# Daughter_ESCON.net
KiCad netlist of a schematic drawn in EAGLE
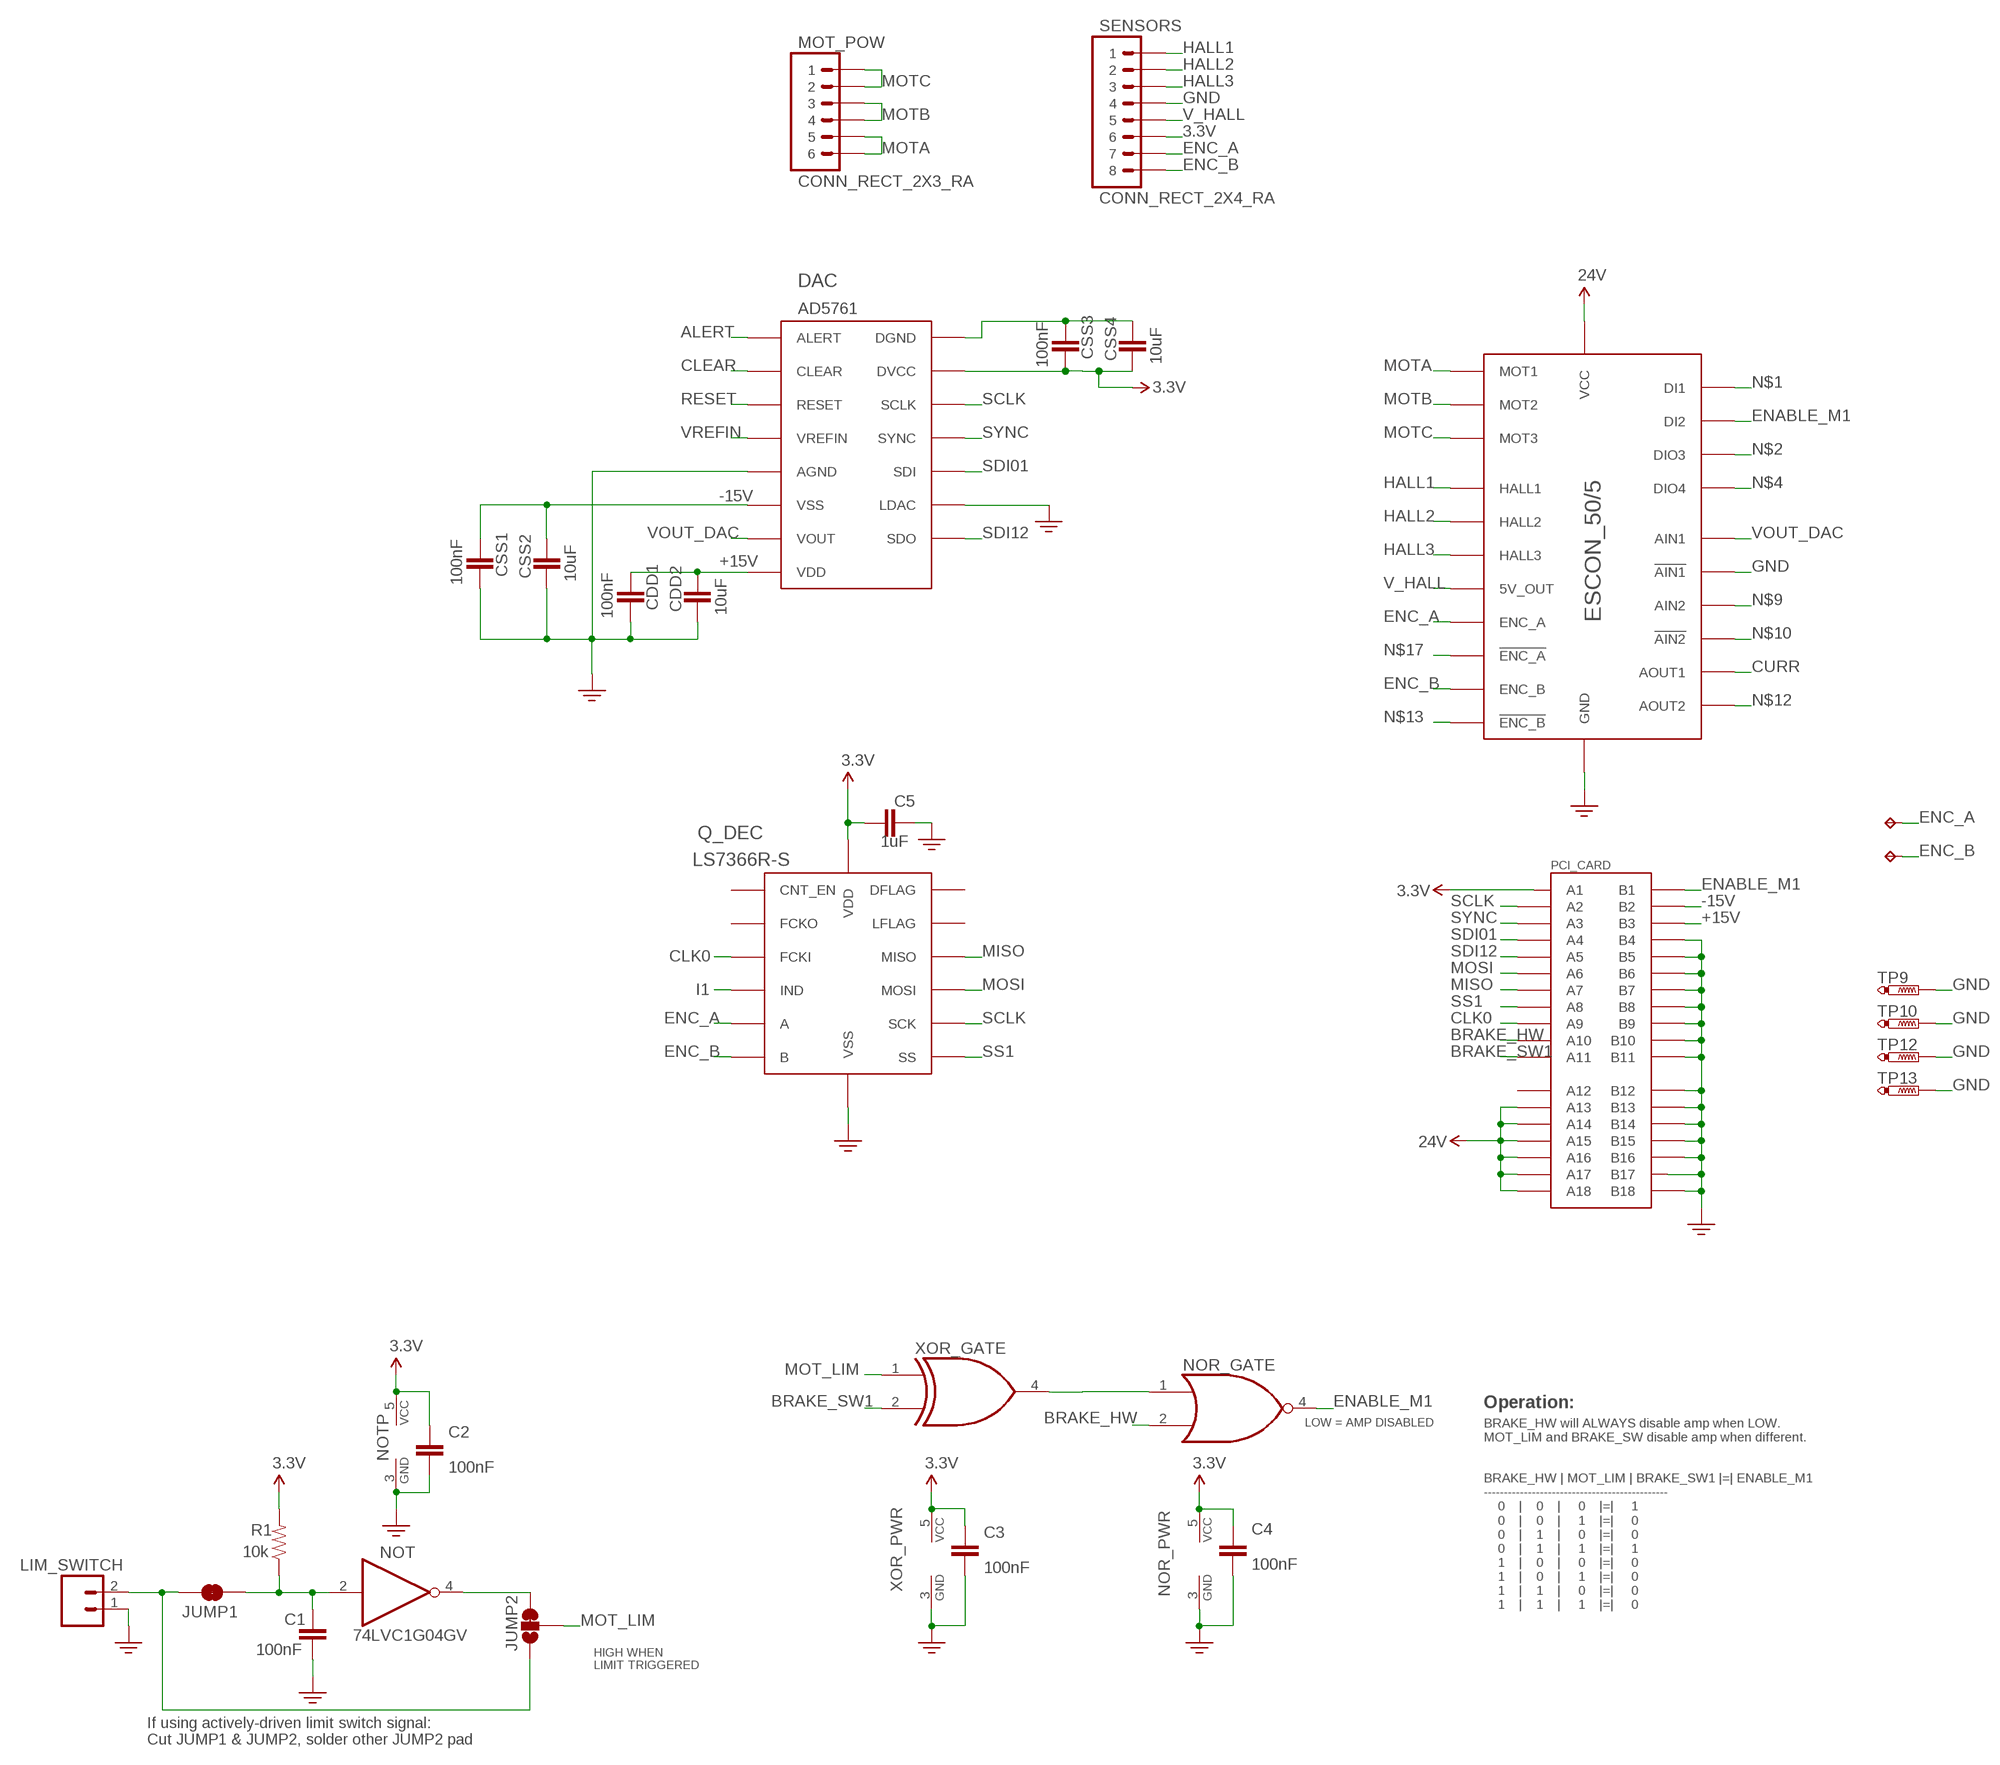
[diagram p0: schematic, sheet 1]

(export (version "E")
  (design (tool "Eeschema 10.0.6"))
  (components
    (comp (ref "A")
      (value "TEST_POINT_0805")
      (footprint "eagle-import:0805-TP")
      (libsource (lib "eagle-import") (part "TEST_POINT_0805"))
    )
    (comp (ref "B")
      (value "TEST_POINT_0805")
      (footprint "eagle-import:0805-TP")
      (libsource (lib "eagle-import") (part "TEST_POINT_0805"))
    )
    (comp (ref "C1")
      (value "100nF")
      (footprint "eagle-import:0603-CAP")
      (libsource (lib "eagle-import") (part "CAP0603-CAP"))
    )
    (comp (ref "C2")
      (value "100nF")
      (footprint "eagle-import:0603-CAP")
      (libsource (lib "eagle-import") (part "CAP0603-CAP"))
    )
    (comp (ref "C3")
      (value "100nF")
      (footprint "eagle-import:0603-CAP")
      (libsource (lib "eagle-import") (part "CAP0603-CAP"))
    )
    (comp (ref "C4")
      (value "100nF")
      (footprint "eagle-import:0603-CAP")
      (libsource (lib "eagle-import") (part "CAP0603-CAP"))
    )
    (comp (ref "C5")
      (value "1uF")
      (footprint "eagle-import:0603-CAP")
      (libsource (lib "eagle-import") (part "CAP0603-CAP"))
    )
    (comp (ref "CDD1")
      (value "100nF")
      (footprint "eagle-import:0603-CAP")
      (libsource (lib "eagle-import") (part "CAP0603-CAP"))
    )
    (comp (ref "CDD2")
      (value "10uF")
      (footprint "eagle-import:C0805K")
      (libsource (lib "eagle-import") (part "CAP0805"))
    )
    (comp (ref "CSS1")
      (value "100nF")
      (footprint "eagle-import:0603-CAP")
      (libsource (lib "eagle-import") (part "CAP0603-CAP"))
    )
    (comp (ref "CSS2")
      (value "10uF")
      (footprint "eagle-import:C0805K")
      (libsource (lib "eagle-import") (part "CAP0805"))
    )
    (comp (ref "CSS3")
      (value "100nF")
      (footprint "eagle-import:0603-CAP")
      (libsource (lib "eagle-import") (part "CAP0603-CAP"))
    )
    (comp (ref "CSS4")
      (value "10uF")
      (footprint "eagle-import:C0805K")
      (libsource (lib "eagle-import") (part "CAP0805"))
    )
    (comp (ref "DAC")
      (value "AD5761")
      (footprint "eagle-import:TSSOP16")
      (libsource (lib "eagle-import") (part "AD5761"))
    )
    (comp (ref "ESCON_50/5")
      (value "ESCON_50-5")
      (footprint "eagle-import:ESCON_50-5")
      (libsource (lib "eagle-import") (part "ESCON_50-5"))
    )
    (comp (ref "JUMP1")
      (value "JUMPER-PAD-2-NC_BY_TRACE")
      (footprint "eagle-import:PAD-JUMPER-2-NC_BY_TRACE_YES_SILK")
      (libsource (lib "eagle-import") (part "JUMPER-PAD-2-NC_BY_TRACE"))
    )
    (comp (ref "JUMP2")
      (value "JUMPER-PAD-3-2OF3_NC_BY_TRACE")
      (footprint "eagle-import:PAD-JUMPER-3-2OF3_NC_BY_TRACE_YES_SILK_FULL_BOX")
      (libsource (lib "eagle-import") (part "JUMPER-PAD-3-2OF3_NC_BY_TRACE"))
    )
    (comp (ref "LIM_SWITCH")
      (value "22-05-7028-02")
      (footprint "eagle-import:7395-02")
      (libsource (lib "eagle-import") (part "22-?-0205-7028"))
    )
    (comp (ref "MOT_POW")
      (value "CONN_RECT_2X3_RA")
      (footprint "eagle-import:2X3-RA")
      (libsource (lib "eagle-import") (part "CONN_RECT_2X3_RA"))
    )
    (comp (ref "NOR")
      (value "NOR-SOT353")
      (footprint "eagle-import:SOT353")
      (libsource (lib "eagle-import") (part "NOR-SOT353"))
    )
    (comp (ref "NOT")
      (value "74LVC1G04GV")
      (footprint "eagle-import:SOT23-5")
      (libsource (lib "eagle-import") (part "741G04DBVLVC"))
    )
    (comp (ref "PCI_CARD")
      (value "PCIE-36-EDGE")
      (footprint "eagle-import:PCIE-36-EDGE")
      (libsource (lib "eagle-import") (part "PCIE-36-EDGE"))
    )
    (comp (ref "Q_DEC")
      (value "LS7366R-S")
      (footprint "eagle-import:SOIC-14")
      (libsource (lib "eagle-import") (part "LS7366R-S"))
    )
    (comp (ref "R1")
      (value "10k")
      (footprint "eagle-import:0603-RES")
      (libsource (lib "eagle-import") (part "RESISTOR-0603"))
    )
    (comp (ref "SENSORS")
      (value "CONN_RECT_2X4_RA")
      (footprint "eagle-import:2X4-RA")
      (libsource (lib "eagle-import") (part "CONN_RECT_2X4_RA"))
    )
    (comp (ref "TP9")
      (value "PTR1TP20R")
      (footprint "eagle-import:TP20R")
      (libsource (lib "eagle-import") (part "PTR1TP20R"))
    )
    (comp (ref "TP10")
      (value "PTR1TP20R")
      (footprint "eagle-import:TP20R")
      (libsource (lib "eagle-import") (part "PTR1TP20R"))
    )
    (comp (ref "TP12")
      (value "PTR1TP20R")
      (footprint "eagle-import:TP20R")
      (libsource (lib "eagle-import") (part "PTR1TP20R"))
    )
    (comp (ref "TP13")
      (value "PTR1TP20R")
      (footprint "eagle-import:TP20R")
      (libsource (lib "eagle-import") (part "PTR1TP20R"))
    )
    (comp (ref "XOR")
      (value "XOR-SOT353")
      (footprint "eagle-import:SOT353")
      (libsource (lib "eagle-import") (part "XOR-SOT353"))
    )
  )
  (nets
    (net (code "1") (name "/+15V") (class "Default")
      (node (ref "CDD1") (pin "1") (pinfunction "1_1") (pintype "passive"))
      (node (ref "CDD2") (pin "1") (pinfunction "1_1") (pintype "passive"))
      (node (ref "DAC") (pin "8") (pinfunction "VDD_8") (pintype "power_in"))
      (node (ref "PCI_CARD") (pin "B3") (pinfunction "B3_B3") (pintype "bidirectional"))
    )
    (net (code "2") (name "/-15V") (class "Default")
      (node (ref "CSS1") (pin "1") (pinfunction "1_1") (pintype "passive"))
      (node (ref "CSS2") (pin "1") (pinfunction "1_1") (pintype "passive"))
      (node (ref "DAC") (pin "6") (pinfunction "VSS_6") (pintype "power_in"))
      (node (ref "PCI_CARD") (pin "B2") (pinfunction "B2_B2") (pintype "bidirectional"))
    )
    (net (code "3") (name "/ALERT") (class "Default")
      (node (ref "DAC") (pin "1") (pinfunction "ALERT_1") (pintype "output"))
    )
    (net (code "4") (name "/BRAKE_HW") (class "Default")
      (node (ref "NOR") (pin "2") (pinfunction "B_2") (pintype "input"))
      (node (ref "PCI_CARD") (pin "A10") (pinfunction "A10_A10") (pintype "bidirectional"))
    )
    (net (code "5") (name "/BRAKE_SW1") (class "Default")
      (node (ref "PCI_CARD") (pin "A11") (pinfunction "A11_A11") (pintype "bidirectional"))
      (node (ref "XOR") (pin "2") (pinfunction "B_2") (pintype "input"))
    )
    (net (code "6") (name "/CLEAR") (class "Default")
      (node (ref "DAC") (pin "2") (pinfunction "CLEAR_2") (pintype "input"))
    )
    (net (code "7") (name "/CLK0") (class "Default")
      (node (ref "PCI_CARD") (pin "A9") (pinfunction "A9_A9") (pintype "bidirectional"))
      (node (ref "Q_DEC") (pin "2") (pinfunction "FCKI_2") (pintype "bidirectional"))
    )
    (net (code "8") (name "/CURR") (class "Default")
      (node (ref "ESCON_50/5") (pin "P$25") (pinfunction "AOUT1_P$25") (pintype "bidirectional"))
    )
    (net (code "9") (name "/ENABLE_M1") (class "Default")
      (node (ref "ESCON_50/5") (pin "P$21") (pinfunction "DI2_P$21") (pintype "bidirectional"))
      (node (ref "NOR") (pin "4") (pinfunction "Y_4") (pintype "output"))
      (node (ref "PCI_CARD") (pin "B1") (pinfunction "B1_B1") (pintype "bidirectional"))
    )
    (net (code "10") (name "/ENC_A") (class "Default")
      (node (ref "A") (pin "1") (pinfunction "TP_1") (pintype "input"))
      (node (ref "ESCON_50/5") (pin "P$12") (pinfunction "ENC_A_P$12") (pintype "bidirectional"))
      (node (ref "Q_DEC") (pin "12") (pinfunction "A_12") (pintype "bidirectional"))
      (node (ref "SENSORS") (pin "7") (pinfunction "7_7") (pintype "passive"))
    )
    (net (code "11") (name "/ENC_B") (class "Default")
      (node (ref "B") (pin "1") (pinfunction "TP_1") (pintype "input"))
      (node (ref "ESCON_50/5") (pin "P$16") (pinfunction "ENC_B_P$16") (pintype "bidirectional"))
      (node (ref "Q_DEC") (pin "11") (pinfunction "B_11") (pintype "bidirectional"))
      (node (ref "SENSORS") (pin "8") (pinfunction "8_8") (pintype "passive"))
    )
    (net (code "12") (name "/HALL1") (class "Default")
      (node (ref "ESCON_50/5") (pin "P$13") (pinfunction "HALL1_P$13") (pintype "bidirectional"))
      (node (ref "SENSORS") (pin "1") (pinfunction "1_1") (pintype "passive"))
    )
    (net (code "13") (name "/HALL2") (class "Default")
      (node (ref "ESCON_50/5") (pin "P$15") (pinfunction "HALL2_P$15") (pintype "bidirectional"))
      (node (ref "SENSORS") (pin "2") (pinfunction "2_2") (pintype "passive"))
    )
    (net (code "14") (name "/HALL3") (class "Default")
      (node (ref "ESCON_50/5") (pin "P$17") (pinfunction "HALL3_P$17") (pintype "bidirectional"))
      (node (ref "SENSORS") (pin "3") (pinfunction "3_3") (pintype "passive"))
    )
    (net (code "15") (name "/I1") (class "Default")
      (node (ref "Q_DEC") (pin "10") (pinfunction "IND_10") (pintype "bidirectional"))
    )
    (net (code "16") (name "/MISO") (class "Default")
      (node (ref "PCI_CARD") (pin "A7") (pinfunction "A7_A7") (pintype "bidirectional"))
      (node (ref "Q_DEC") (pin "6") (pinfunction "MISO_6") (pintype "bidirectional"))
    )
    (net (code "17") (name "/MOSI") (class "Default")
      (node (ref "PCI_CARD") (pin "A6") (pinfunction "A6_A6") (pintype "bidirectional"))
      (node (ref "Q_DEC") (pin "7") (pinfunction "MOSI_7") (pintype "bidirectional"))
    )
    (net (code "18") (name "/MOTA") (class "Default")
      (node (ref "ESCON_50/5") (pin "P$1") (pinfunction "MOT1_P$1") (pintype "bidirectional"))
      (node (ref "ESCON_50/5") (pin "P$2") (pinfunction "MOT1_P$2") (pintype "bidirectional"))
      (node (ref "MOT_POW") (pin "5") (pinfunction "5_5") (pintype "passive"))
      (node (ref "MOT_POW") (pin "6") (pinfunction "6_6") (pintype "passive"))
    )
    (net (code "19") (name "/MOTB") (class "Default")
      (node (ref "ESCON_50/5") (pin "P$3") (pinfunction "MOT2_P$3") (pintype "bidirectional"))
      (node (ref "ESCON_50/5") (pin "P$4") (pinfunction "MOT2_P$4") (pintype "bidirectional"))
      (node (ref "MOT_POW") (pin "3") (pinfunction "3_3") (pintype "passive"))
      (node (ref "MOT_POW") (pin "4") (pinfunction "4_4") (pintype "passive"))
    )
    (net (code "20") (name "/MOTC") (class "Default")
      (node (ref "ESCON_50/5") (pin "P$5") (pinfunction "MOT3_P$5") (pintype "bidirectional"))
      (node (ref "ESCON_50/5") (pin "P$6") (pinfunction "MOT3_P$6") (pintype "bidirectional"))
      (node (ref "MOT_POW") (pin "1") (pinfunction "1_1") (pintype "passive"))
      (node (ref "MOT_POW") (pin "2") (pinfunction "2_2") (pintype "passive"))
    )
    (net (code "21") (name "/MOT_LIM") (class "Default")
      (node (ref "JUMP2") (pin "2") (pinfunction "2_2") (pintype "passive"))
      (node (ref "XOR") (pin "1") (pinfunction "A_1") (pintype "input"))
    )
    (net (code "22") (name "/N$1") (class "Default")
      (node (ref "ESCON_50/5") (pin "P$22") (pinfunction "DI1_P$22") (pintype "bidirectional"))
    )
    (net (code "23") (name "/N$2") (class "Default")
      (node (ref "ESCON_50/5") (pin "P$20") (pinfunction "DIO3_P$20") (pintype "bidirectional"))
    )
    (net (code "24") (name "/N$4") (class "Default")
      (node (ref "ESCON_50/5") (pin "P$19") (pinfunction "DIO4_P$19") (pintype "bidirectional"))
    )
    (net (code "25") (name "/N$9") (class "Default")
      (node (ref "ESCON_50/5") (pin "P$27") (pinfunction "AIN2_P$27") (pintype "bidirectional"))
    )
    (net (code "26") (name "/N$10") (class "Default")
      (node (ref "ESCON_50/5") (pin "P$26") (pinfunction "~{AIN2}_P$26") (pintype "bidirectional"))
    )
    (net (code "27") (name "/N$12") (class "Default")
      (node (ref "ESCON_50/5") (pin "P$24") (pinfunction "AOUT2_P$24") (pintype "bidirectional"))
    )
    (net (code "28") (name "/N$13") (class "Default")
      (node (ref "ESCON_50/5") (pin "P$18") (pinfunction "~{ENC_B}_P$18") (pintype "bidirectional"))
    )
    (net (code "29") (name "/N$17") (class "Default")
      (node (ref "ESCON_50/5") (pin "P$14") (pinfunction "~{ENC_A}_P$14") (pintype "bidirectional"))
    )
    (net (code "30") (name "/RESET") (class "Default")
      (node (ref "DAC") (pin "3") (pinfunction "RESET_3") (pintype "input"))
    )
    (net (code "31") (name "/SCLK") (class "Default")
      (node (ref "DAC") (pin "14") (pinfunction "SCLK_14") (pintype "input"))
      (node (ref "PCI_CARD") (pin "A2") (pinfunction "A2_A2") (pintype "bidirectional"))
      (node (ref "Q_DEC") (pin "5") (pinfunction "SCK_5") (pintype "bidirectional"))
    )
    (net (code "32") (name "/SDI01") (class "Default")
      (node (ref "DAC") (pin "12") (pinfunction "SDI_12") (pintype "input"))
      (node (ref "PCI_CARD") (pin "A4") (pinfunction "A4_A4") (pintype "bidirectional"))
    )
    (net (code "33") (name "/SDI12") (class "Default")
      (node (ref "DAC") (pin "10") (pinfunction "SDO_10") (pintype "output"))
      (node (ref "PCI_CARD") (pin "A5") (pinfunction "A5_A5") (pintype "bidirectional"))
    )
    (net (code "34") (name "/SS1") (class "Default")
      (node (ref "PCI_CARD") (pin "A8") (pinfunction "A8_A8") (pintype "bidirectional"))
      (node (ref "Q_DEC") (pin "4") (pinfunction "SS_4") (pintype "bidirectional"))
    )
    (net (code "35") (name "/SYNC") (class "Default")
      (node (ref "DAC") (pin "13") (pinfunction "SYNC_13") (pintype "input"))
      (node (ref "PCI_CARD") (pin "A3") (pinfunction "A3_A3") (pintype "bidirectional"))
    )
    (net (code "36") (name "/VOUT_DAC") (class "Default")
      (node (ref "DAC") (pin "7") (pinfunction "VOUT_7") (pintype "power_in"))
      (node (ref "ESCON_50/5") (pin "P$29") (pinfunction "AIN1_P$29") (pintype "bidirectional"))
    )
    (net (code "37") (name "/VREFIN") (class "Default")
      (node (ref "DAC") (pin "4") (pinfunction "VREFIN_4") (pintype "bidirectional"))
    )
    (net (code "38") (name "/V_HALL") (class "Default")
      (node (ref "ESCON_50/5") (pin "P$11") (pinfunction "5V_OUT_P$11") (pintype "bidirectional"))
      (node (ref "SENSORS") (pin "5") (pinfunction "5_5") (pintype "passive"))
    )
    (net (code "39") (name "3.3V") (class "Default")
      (node (ref "C2") (pin "1") (pinfunction "1_1") (pintype "passive"))
      (node (ref "C3") (pin "1") (pinfunction "1_1") (pintype "passive"))
      (node (ref "C4") (pin "1") (pinfunction "1_1") (pintype "passive"))
      (node (ref "C5") (pin "1") (pinfunction "1_1") (pintype "passive"))
      (node (ref "CSS3") (pin "2") (pinfunction "2_2") (pintype "passive"))
      (node (ref "CSS4") (pin "2") (pinfunction "2_2") (pintype "passive"))
      (node (ref "DAC") (pin "15") (pinfunction "DVCC_15") (pintype "power_in"))
      (node (ref "NOR") (pin "5") (pinfunction "VCC_5") (pintype "power_in"))
      (node (ref "NOT") (pin "5") (pinfunction "VCC_5") (pintype "power_in"))
      (node (ref "PCI_CARD") (pin "A1") (pinfunction "A1_A1") (pintype "bidirectional"))
      (node (ref "Q_DEC") (pin "14") (pinfunction "VDD_14") (pintype "bidirectional"))
      (node (ref "R1") (pin "2") (pinfunction "2_2") (pintype "passive"))
      (node (ref "SENSORS") (pin "6") (pinfunction "6_6") (pintype "passive"))
      (node (ref "XOR") (pin "5") (pinfunction "VCC_5") (pintype "power_in"))
    )
    (net (code "40") (name "24V") (class "Default")
      (node (ref "ESCON_50/5") (pin "P$7") (pinfunction "VCC_P$7") (pintype "bidirectional"))
      (node (ref "ESCON_50/5") (pin "P$8") (pinfunction "VCC_P$8") (pintype "bidirectional"))
      (node (ref "PCI_CARD") (pin "A13") (pinfunction "A13_A13") (pintype "bidirectional"))
      (node (ref "PCI_CARD") (pin "A14") (pinfunction "A14_A14") (pintype "bidirectional"))
      (node (ref "PCI_CARD") (pin "A15") (pinfunction "A15_A15") (pintype "bidirectional"))
      (node (ref "PCI_CARD") (pin "A16") (pinfunction "A16_A16") (pintype "bidirectional"))
      (node (ref "PCI_CARD") (pin "A17") (pinfunction "A17_A17") (pintype "bidirectional"))
      (node (ref "PCI_CARD") (pin "A18") (pinfunction "A18_A18") (pintype "bidirectional"))
    )
    (net (code "41") (name "GND2") (class "Default")
      (node (ref "C1") (pin "2") (pinfunction "2_2") (pintype "passive"))
      (node (ref "C2") (pin "2") (pinfunction "2_2") (pintype "passive"))
      (node (ref "C3") (pin "2") (pinfunction "2_2") (pintype "passive"))
      (node (ref "C4") (pin "2") (pinfunction "2_2") (pintype "passive"))
      (node (ref "C5") (pin "2") (pinfunction "2_2") (pintype "passive"))
      (node (ref "CDD1") (pin "2") (pinfunction "2_2") (pintype "passive"))
      (node (ref "CDD2") (pin "2") (pinfunction "2_2") (pintype "passive"))
      (node (ref "CSS1") (pin "2") (pinfunction "2_2") (pintype "passive"))
      (node (ref "CSS2") (pin "2") (pinfunction "2_2") (pintype "passive"))
      (node (ref "CSS3") (pin "1") (pinfunction "1_1") (pintype "passive"))
      (node (ref "CSS4") (pin "1") (pinfunction "1_1") (pintype "passive"))
      (node (ref "DAC") (pin "11") (pinfunction "LDAC_11") (pintype "input"))
      (node (ref "DAC") (pin "16") (pinfunction "DGND_16") (pintype "power_in"))
      (node (ref "DAC") (pin "5") (pinfunction "AGND_5") (pintype "power_in"))
      (node (ref "ESCON_50/5") (pin "P$10") (pinfunction "GND_P$10") (pintype "bidirectional"))
      (node (ref "ESCON_50/5") (pin "P$23") (pinfunction "GND_P$23") (pintype "bidirectional"))
      (node (ref "ESCON_50/5") (pin "P$28") (pinfunction "~{AIN1}_P$28") (pintype "bidirectional"))
      (node (ref "ESCON_50/5") (pin "P$9") (pinfunction "GND_P$9") (pintype "bidirectional"))
      (node (ref "LIM_SWITCH") (pin "1") (pinfunction "1_1") (pintype "passive"))
      (node (ref "NOR") (pin "3") (pinfunction "GND_3") (pintype "power_in"))
      (node (ref "NOT") (pin "3") (pinfunction "GND_3") (pintype "power_in"))
      (node (ref "PCI_CARD") (pin "B10") (pinfunction "B10_B10") (pintype "bidirectional"))
      (node (ref "PCI_CARD") (pin "B11") (pinfunction "B11_B11") (pintype "bidirectional"))
      (node (ref "PCI_CARD") (pin "B12") (pinfunction "B12_B12") (pintype "bidirectional"))
      (node (ref "PCI_CARD") (pin "B13") (pinfunction "B13_B13") (pintype "bidirectional"))
      (node (ref "PCI_CARD") (pin "B14") (pinfunction "B14_B14") (pintype "bidirectional"))
      (node (ref "PCI_CARD") (pin "B15") (pinfunction "B15_B15") (pintype "bidirectional"))
      (node (ref "PCI_CARD") (pin "B16") (pinfunction "B16_B16") (pintype "bidirectional"))
      (node (ref "PCI_CARD") (pin "B17") (pinfunction "B17_B17") (pintype "bidirectional"))
      (node (ref "PCI_CARD") (pin "B18") (pinfunction "B18_B18") (pintype "bidirectional"))
      (node (ref "PCI_CARD") (pin "B4") (pinfunction "B4_B4") (pintype "bidirectional"))
      (node (ref "PCI_CARD") (pin "B5") (pinfunction "B5_B5") (pintype "bidirectional"))
      (node (ref "PCI_CARD") (pin "B6") (pinfunction "B6_B6") (pintype "bidirectional"))
      (node (ref "PCI_CARD") (pin "B7") (pinfunction "B7_B7") (pintype "bidirectional"))
      (node (ref "PCI_CARD") (pin "B8") (pinfunction "B8_B8") (pintype "bidirectional"))
      (node (ref "PCI_CARD") (pin "B9") (pinfunction "B9_B9") (pintype "bidirectional"))
      (node (ref "Q_DEC") (pin "3") (pinfunction "VSS_3") (pintype "bidirectional"))
      (node (ref "SENSORS") (pin "4") (pinfunction "4_4") (pintype "passive"))
      (node (ref "TP10") (pin "TP") (pinfunction "TP_TP") (pintype "input"))
      (node (ref "TP12") (pin "TP") (pinfunction "TP_TP") (pintype "input"))
      (node (ref "TP13") (pin "TP") (pinfunction "TP_TP") (pintype "input"))
      (node (ref "TP9") (pin "TP") (pinfunction "TP_TP") (pintype "input"))
      (node (ref "XOR") (pin "3") (pinfunction "GND_3") (pintype "power_in"))
    )
    (net (code "42") (name "Net-(JUMP1-Pad1)") (class "Default")
      (node (ref "JUMP1") (pin "1") (pinfunction "1_1") (pintype "passive"))
      (node (ref "JUMP2") (pin "1") (pinfunction "1_1") (pintype "passive"))
      (node (ref "LIM_SWITCH") (pin "2") (pinfunction "2_2") (pintype "passive"))
    )
    (net (code "43") (name "Net-(NORA-A)") (class "Default")
      (node (ref "NOR") (pin "1") (pinfunction "A_1") (pintype "input"))
      (node (ref "XOR") (pin "4") (pinfunction "Y_4") (pintype "output"))
    )
    (net (code "44") (name "Net-(NOTA-I)") (class "Default")
      (node (ref "C1") (pin "1") (pinfunction "1_1") (pintype "passive"))
      (node (ref "JUMP1") (pin "2") (pinfunction "2_2") (pintype "passive"))
      (node (ref "NOT") (pin "2") (pinfunction "I_2") (pintype "input"))
      (node (ref "R1") (pin "1") (pinfunction "1_1") (pintype "passive"))
    )
    (net (code "45") (name "Net-(NOTA-O)") (class "Default")
      (node (ref "JUMP2") (pin "3") (pinfunction "3_3") (pintype "passive"))
      (node (ref "NOT") (pin "4") (pinfunction "O_4") (pintype "output"))
    )
    (net (code "46") (name "unconnected-(PCI_CARD-PadA12)") (class "Default")
      (node (ref "PCI_CARD") (pin "A12") (pinfunction "A12_A12") (pintype "bidirectional"))
    )
    (net (code "47") (name "unconnected-(Q_DEC-CNT_EN-Pad13)") (class "Default")
      (node (ref "Q_DEC") (pin "13") (pinfunction "CNT_EN_13") (pintype "bidirectional"))
    )
    (net (code "48") (name "unconnected-(Q_DEC-DFLAG-Pad9)") (class "Default")
      (node (ref "Q_DEC") (pin "9") (pinfunction "DFLAG_9") (pintype "bidirectional"))
    )
    (net (code "49") (name "unconnected-(Q_DEC-FCKO-Pad1)") (class "Default")
      (node (ref "Q_DEC") (pin "1") (pinfunction "FCKO_1") (pintype "bidirectional"))
    )
    (net (code "50") (name "unconnected-(Q_DEC-LFLAG-Pad8)") (class "Default")
      (node (ref "Q_DEC") (pin "8") (pinfunction "LFLAG_8") (pintype "bidirectional"))
    )
  )
)
